# alcohal_sensor_and_send_sms_using_gsm.net
KiCad netlist of a schematic drawn in EAGLE
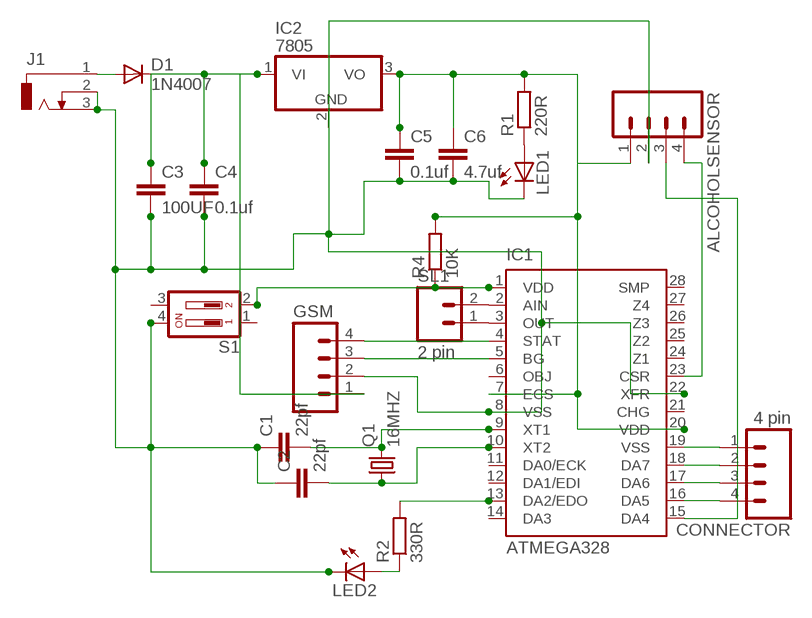
[diagram p0: schematic, sheet 1]

(export (version "E")
  (design (tool "Eeschema 10.0.6"))
  (components
    (comp (ref "ALCOHOLSENSOR")
      (value "M04")
      (footprint "eagle-import:04P")
      (fields (field (name "OC_FARNELL") "unknown") (field (name "OC_NEWARK") "unknown"))
      (libsource (lib "eagle-import") (part "M04"))
    )
    (comp (ref "C1")
      (value "22pf")
      (footprint "eagle-import:C2.5-2")
      (libsource (lib "eagle-import") (part "C2.5/2"))
    )
    (comp (ref "C2")
      (value "22pf")
      (footprint "eagle-import:C2.5-2")
      (libsource (lib "eagle-import") (part "C2.5/2"))
    )
    (comp (ref "C3")
      (value "100UF")
      (footprint "eagle-import:C2.5-2")
      (libsource (lib "eagle-import") (part "C2.5/2"))
    )
    (comp (ref "C4")
      (value "0.1uf")
      (footprint "eagle-import:C2.5-2")
      (libsource (lib "eagle-import") (part "C2.5/2"))
    )
    (comp (ref "C5")
      (value "0.1uf")
      (footprint "eagle-import:C2.5-2")
      (libsource (lib "eagle-import") (part "C2.5/2"))
    )
    (comp (ref "C6")
      (value "4.7uf")
      (footprint "eagle-import:C2.5-2")
      (libsource (lib "eagle-import") (part "C2.5/2"))
    )
    (comp (ref "CONNECTOR")
      (value "4 pin")
      (footprint "eagle-import:04P")
      (fields (field (name "OC_FARNELL") "unknown") (field (name "OC_NEWARK") "unknown"))
      (libsource (lib "eagle-import") (part "M04"))
    )
    (comp (ref "D1")
      (value "1N4007")
      (footprint "eagle-import:DO41-10")
      (libsource (lib "eagle-import") (part "1N4004"))
    )
    (comp (ref "GSM")
      (value "M04")
      (footprint "eagle-import:04P")
      (libsource (lib "eagle-import") (part "M04"))
    )
    (comp (ref "IC1")
      (value "ATMEGA328")
      (footprint "eagle-import:DIL28-3")
      (libsource (lib "eagle-import") (part "QT9701BD"))
    )
    (comp (ref "IC2")
      (value "7805")
      (footprint "eagle-import:TO220V")
      (libsource (lib "eagle-import") (part "78TV6"))
    )
    (comp (ref "J1")
      (value "DCJ0303")
      (footprint "eagle-import:DCJ0303")
      (libsource (lib "eagle-import") (part "DCJ0303"))
    )
    (comp (ref "LED1")
      (value "LED3MM")
      (footprint "eagle-import:LED3MM")
      (libsource (lib "eagle-import") (part "LED3MM"))
    )
    (comp (ref "LED2")
      (value "LED3MM")
      (footprint "eagle-import:LED3MM")
      (libsource (lib "eagle-import") (part "LED3MM"))
    )
    (comp (ref "Q1")
      (value "16MHZ")
      (footprint "eagle-import:HC49_S")
      (libsource (lib "eagle-import") (part "CRYSTALHC49S"))
    )
    (comp (ref "R1")
      (value "220R")
      (footprint "eagle-import:0207_10")
      (libsource (lib "eagle-import") (part "R-EU_0207/10"))
    )
    (comp (ref "R2")
      (value "330R")
      (footprint "eagle-import:0207_10")
      (libsource (lib "eagle-import") (part "R-EU_0207/10"))
    )
    (comp (ref "R4")
      (value "10K")
      (footprint "eagle-import:0207_10")
      (libsource (lib "eagle-import") (part "R-EU_0207/10"))
    )
    (comp (ref "S1")
      (value "DP02")
      (footprint "eagle-import:DP-02")
      (fields (field (name "MPN") "MCDP02"))
      (libsource (lib "eagle-import") (part "DP02"))
    )
    (comp (ref "SL1")
      (value "2 pin")
      (footprint "eagle-import:02P")
      (libsource (lib "eagle-import") (part "M02"))
    )
  )
  (nets
    (net (code "1") (name "Net-(CONNECTOR-Pad1)") (class "Default")
      (node (ref "CONNECTOR") (pin "1") (pinfunction "1_1") (pintype "passive"))
      (node (ref "IC1") (pin "19") (pinfunction "VSS_19") (pintype "input"))
    )
    (net (code "2") (name "Net-(D1-PadA)") (class "Default")
      (node (ref "D1") (pin "A") (pinfunction "A_A") (pintype "passive"))
      (node (ref "J1") (pin "1") (pinfunction "1_1") (pintype "passive"))
    )
    (net (code "3") (name "Net-(IC1-AIN)") (class "Default")
      (node (ref "IC1") (pin "2") (pinfunction "AIN_2") (pintype "input"))
      (node (ref "SL1") (pin "2") (pinfunction "2_2") (pintype "passive"))
    )
    (net (code "4") (name "Net-(IC1-BG)") (class "Default")
      (node (ref "GSM") (pin "3") (pinfunction "3_3") (pintype "passive"))
      (node (ref "IC1") (pin "5") (pinfunction "BG_5") (pintype "input"))
    )
    (net (code "5") (name "Net-(IC1-CSR)") (class "Default")
      (node (ref "ALCOHOLSENSOR") (pin "4") (pinfunction "4_4") (pintype "passive"))
      (node (ref "IC1") (pin "23") (pinfunction "CSR_23") (pintype "output"))
    )
    (net (code "6") (name "Net-(IC1-DA2{slash}EDO)") (class "Default")
      (node (ref "IC1") (pin "13") (pinfunction "DA2/EDO_13") (pintype "output"))
      (node (ref "R2") (pin "2") (pinfunction "2_2") (pintype "passive"))
    )
    (net (code "7") (name "Net-(IC1-DA4)") (class "Default")
      (node (ref "ALCOHOLSENSOR") (pin "3") (pinfunction "3_3") (pintype "passive"))
      (node (ref "IC1") (pin "15") (pinfunction "DA4_15") (pintype "output"))
    )
    (net (code "8") (name "Net-(IC1-DA5)") (class "Default")
      (node (ref "CONNECTOR") (pin "4") (pinfunction "4_4") (pintype "passive"))
      (node (ref "IC1") (pin "16") (pinfunction "DA5_16") (pintype "output"))
    )
    (net (code "9") (name "Net-(IC1-DA6)") (class "Default")
      (node (ref "CONNECTOR") (pin "3") (pinfunction "3_3") (pintype "passive"))
      (node (ref "IC1") (pin "17") (pinfunction "DA6_17") (pintype "output"))
    )
    (net (code "10") (name "Net-(IC1-DA7)") (class "Default")
      (node (ref "CONNECTOR") (pin "2") (pinfunction "2_2") (pintype "passive"))
      (node (ref "IC1") (pin "18") (pinfunction "DA7_18") (pintype "output"))
    )
    (net (code "11") (name "Net-(IC1-ECS)") (class "Default")
      (node (ref "ALCOHOLSENSOR") (pin "1") (pinfunction "1_1") (pintype "passive"))
      (node (ref "C5") (pin "1") (pinfunction "1_1") (pintype "passive"))
      (node (ref "C6") (pin "1") (pinfunction "1_1") (pintype "passive"))
      (node (ref "IC1") (pin "20") (pinfunction "VDD_20") (pintype "input"))
      (node (ref "IC1") (pin "7") (pinfunction "ECS_7") (pintype "output"))
      (node (ref "IC2") (pin "3") (pinfunction "VO_3") (pintype "passive"))
      (node (ref "R1") (pin "2") (pinfunction "2_2") (pintype "passive"))
      (node (ref "R4") (pin "2") (pinfunction "2_2") (pintype "passive"))
    )
    (net (code "12") (name "Net-(IC1-OUT)") (class "Default")
      (node (ref "IC1") (pin "3") (pinfunction "OUT_3") (pintype "output"))
      (node (ref "SL1") (pin "1") (pinfunction "1_1") (pintype "passive"))
    )
    (net (code "13") (name "Net-(IC1-STAT)") (class "Default")
      (node (ref "GSM") (pin "4") (pinfunction "4_4") (pintype "passive"))
      (node (ref "IC1") (pin "4") (pinfunction "STAT_4") (pintype "output"))
    )
    (net (code "14") (name "Net-(IC1-VDD-Pad1)") (class "Default")
      (node (ref "IC1") (pin "1") (pinfunction "VDD_1") (pintype "input"))
      (node (ref "R4") (pin "1") (pinfunction "1_1") (pintype "passive"))
      (node (ref "S1") (pin "2") (pinfunction "2_2") (pintype "passive"))
    )
    (net (code "15") (name "Net-(IC1-XFR)") (class "Default")
      (node (ref "ALCOHOLSENSOR") (pin "2") (pinfunction "2_2") (pintype "passive"))
      (node (ref "C1") (pin "1") (pinfunction "1_1") (pintype "passive"))
      (node (ref "C2") (pin "1") (pinfunction "1_1") (pintype "passive"))
      (node (ref "C3") (pin "2") (pinfunction "2_2") (pintype "passive"))
      (node (ref "C4") (pin "2") (pinfunction "2_2") (pintype "passive"))
      (node (ref "C5") (pin "2") (pinfunction "2_2") (pintype "passive"))
      (node (ref "C6") (pin "2") (pinfunction "2_2") (pintype "passive"))
      (node (ref "GSM") (pin "2") (pinfunction "2_2") (pintype "passive"))
      (node (ref "IC1") (pin "22") (pinfunction "XFR_22") (pintype "output"))
      (node (ref "IC1") (pin "8") (pinfunction "VSS_8") (pintype "input"))
      (node (ref "IC2") (pin "2") (pinfunction "GND_2") (pintype "passive"))
      (node (ref "J1") (pin "2") (pinfunction "2_2") (pintype "passive"))
      (node (ref "J1") (pin "3") (pinfunction "3_3") (pintype "passive"))
      (node (ref "LED1") (pin "K") (pinfunction "C_K") (pintype "passive"))
      (node (ref "LED2") (pin "K") (pinfunction "C_K") (pintype "passive"))
      (node (ref "S1") (pin "4") (pinfunction "4_4") (pintype "passive"))
    )
    (net (code "16") (name "Net-(IC1-XT1)") (class "Default")
      (node (ref "C1") (pin "2") (pinfunction "2_2") (pintype "passive"))
      (node (ref "IC1") (pin "9") (pinfunction "XT1_9") (pintype "input"))
      (node (ref "Q1") (pin "2") (pinfunction "2_2") (pintype "passive"))
    )
    (net (code "17") (name "Net-(IC1-XT2)") (class "Default")
      (node (ref "C2") (pin "2") (pinfunction "2_2") (pintype "passive"))
      (node (ref "IC1") (pin "10") (pinfunction "XT2_10") (pintype "output"))
      (node (ref "Q1") (pin "1") (pinfunction "1_1") (pintype "passive"))
    )
    (net (code "18") (name "Net-(IC2-VI)") (class "Default")
      (node (ref "C3") (pin "1") (pinfunction "1_1") (pintype "passive"))
      (node (ref "C4") (pin "1") (pinfunction "1_1") (pintype "passive"))
      (node (ref "D1") (pin "C") (pinfunction "C_C") (pintype "passive"))
      (node (ref "GSM") (pin "1") (pinfunction "1_1") (pintype "passive"))
      (node (ref "IC2") (pin "1") (pinfunction "VI_1") (pintype "input"))
    )
    (net (code "19") (name "Net-(LED1-PadA)") (class "Default")
      (node (ref "LED1") (pin "A") (pinfunction "A_A") (pintype "passive"))
      (node (ref "R1") (pin "1") (pinfunction "1_1") (pintype "passive"))
    )
    (net (code "20") (name "Net-(LED2-PadA)") (class "Default")
      (node (ref "LED2") (pin "A") (pinfunction "A_A") (pintype "passive"))
      (node (ref "R2") (pin "1") (pinfunction "1_1") (pintype "passive"))
    )
    (net (code "21") (name "unconnected-(IC1-CHG-Pad21)") (class "Default")
      (node (ref "IC1") (pin "21") (pinfunction "CHG_21") (pintype "output"))
    )
    (net (code "22") (name "unconnected-(IC1-DA0{slash}ECK-Pad11)") (class "Default")
      (node (ref "IC1") (pin "11") (pinfunction "DA0/ECK_11") (pintype "output"))
    )
    (net (code "23") (name "unconnected-(IC1-DA1{slash}EDI-Pad12)") (class "Default")
      (node (ref "IC1") (pin "12") (pinfunction "DA1/EDI_12") (pintype "output"))
    )
    (net (code "24") (name "unconnected-(IC1-DA3-Pad14)") (class "Default")
      (node (ref "IC1") (pin "14") (pinfunction "DA3_14") (pintype "output"))
    )
    (net (code "25") (name "unconnected-(IC1-OBJ-Pad6)") (class "Default")
      (node (ref "IC1") (pin "6") (pinfunction "OBJ_6") (pintype "input"))
    )
    (net (code "26") (name "unconnected-(IC1-SMP-Pad28)") (class "Default")
      (node (ref "IC1") (pin "28") (pinfunction "SMP_28") (pintype "output"))
    )
    (net (code "27") (name "unconnected-(IC1-Z1-Pad24)") (class "Default")
      (node (ref "IC1") (pin "24") (pinfunction "Z1_24") (pintype "output"))
    )
    (net (code "28") (name "unconnected-(IC1-Z2-Pad25)") (class "Default")
      (node (ref "IC1") (pin "25") (pinfunction "Z2_25") (pintype "output"))
    )
    (net (code "29") (name "unconnected-(IC1-Z3-Pad26)") (class "Default")
      (node (ref "IC1") (pin "26") (pinfunction "Z3_26") (pintype "output"))
    )
    (net (code "30") (name "unconnected-(IC1-Z4-Pad27)") (class "Default")
      (node (ref "IC1") (pin "27") (pinfunction "Z4_27") (pintype "output"))
    )
    (net (code "31") (name "unconnected-(S1-Pad1)") (class "Default")
      (node (ref "S1") (pin "1") (pinfunction "1_1") (pintype "passive"))
    )
    (net (code "32") (name "unconnected-(S1-Pad3)") (class "Default")
      (node (ref "S1") (pin "3") (pinfunction "3_3") (pintype "passive"))
    )
  )
)
